# Bias_Lighting_Controller_Schematic.net
KiCad netlist of a schematic drawn in EAGLE
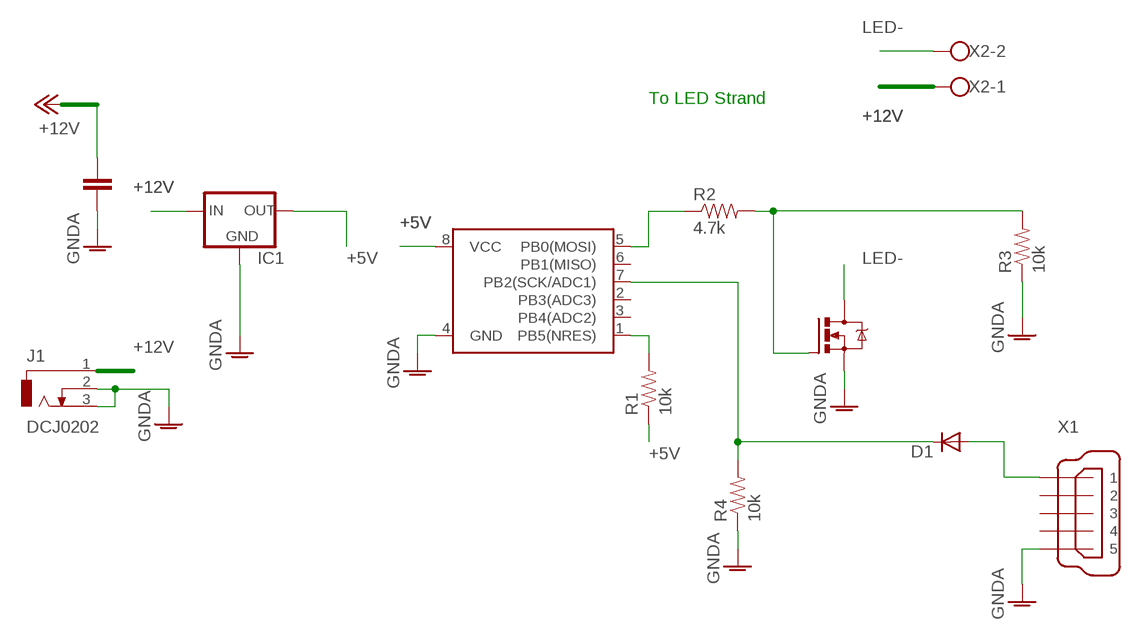
[diagram p0: schematic, sheet 1]

(export (version "E")
  (design (tool "Eeschema 10.0.6"))
  (components
    (comp (ref "C1")
      (value "CAP1206")
      (footprint "eagle-import:1206")
      (libsource (lib "eagle-import") (part "CAP1206"))
    )
    (comp (ref "D1")
      (value "DIODESMA")
      (footprint "eagle-import:SMA-DIODE")
      (libsource (lib "eagle-import") (part "DIODESMA"))
    )
    (comp (ref "IC1")
      (value "78LXX")
      (footprint "eagle-import:78LXX")
      (libsource (lib "eagle-import") (part "78LXX"))
    )
    (comp (ref "IRF740_MOSFET")
      (value "IRF740")
      (footprint "eagle-import:TO220BV")
      (libsource (lib "eagle-import") (part "IRF740"))
    )
    (comp (ref "J1")
      (value "DCJ0202")
      (footprint "eagle-import:DCJ0202")
      (libsource (lib "eagle-import") (part "DCJ0202"))
    )
    (comp (ref "R1")
      (value "10k")
      (footprint "eagle-import:1206")
      (libsource (lib "eagle-import") (part "RESISTOR1206"))
    )
    (comp (ref "R2")
      (value "4.7k")
      (footprint "eagle-import:1206")
      (libsource (lib "eagle-import") (part "RESISTOR1206"))
    )
    (comp (ref "R3")
      (value "10k")
      (footprint "eagle-import:1206")
      (libsource (lib "eagle-import") (part "RESISTOR1206"))
    )
    (comp (ref "R4")
      (value "10k")
      (footprint "eagle-import:1206")
      (libsource (lib "eagle-import") (part "RESISTOR1206"))
    )
    (comp (ref "U$1")
      (value "ATTINY45DIP8")
      (footprint "eagle-import:DIP08")
      (libsource (lib "eagle-import") (part "ATTINY45DIP8"))
    )
    (comp (ref "X1")
      (value "MINI-USB-UX60-MB-5ST")
      (footprint "eagle-import:UX60-MB-5ST")
      (libsource (lib "eagle-import") (part "MINI-USB-UX60-MB-5ST"))
    )
    (comp (ref "X2")
      (value "W237-102")
      (footprint "eagle-import:W237-102")
      (fields (field (name "MPN") "237-102"))
      (libsource (lib "eagle-import") (part "W237-102"))
    )
  )
  (nets
    (net (code "1") (name "+12V") (class "Default")
      (node (ref "C1") (pin "2") (pinfunction "2_2") (pintype "passive"))
      (node (ref "IC1") (pin "IN") (pinfunction "IN_IN") (pintype "input"))
      (node (ref "J1") (pin "1") (pinfunction "1_1") (pintype "passive"))
      (node (ref "X2") (pin "1") (pinfunction "KL_1") (pintype "passive"))
    )
    (net (code "2") (name "/+5V") (class "Default")
      (node (ref "IC1") (pin "OUT") (pinfunction "OUT_OUT") (pintype "passive"))
      (node (ref "R1") (pin "1") (pinfunction "1_1") (pintype "passive"))
      (node (ref "U$1") (pin "8") (pinfunction "VCC_8") (pintype "bidirectional"))
    )
    (net (code "3") (name "/LED-") (class "Default")
      (node (ref "IRF740_MOSFET") (pin "D") (pinfunction "D_D") (pintype "passive"))
      (node (ref "X2") (pin "2") (pinfunction "KL_2") (pintype "passive"))
    )
    (net (code "4") (name "GNDA") (class "Default")
      (node (ref "C1") (pin "1") (pinfunction "1_1") (pintype "passive"))
      (node (ref "IC1") (pin "GND") (pinfunction "GND_GND") (pintype "input"))
      (node (ref "IRF740_MOSFET") (pin "S") (pinfunction "S_S") (pintype "passive"))
      (node (ref "J1") (pin "2") (pinfunction "2_2") (pintype "passive"))
      (node (ref "J1") (pin "3") (pinfunction "3_3") (pintype "passive"))
      (node (ref "R3") (pin "1") (pinfunction "1_1") (pintype "passive"))
      (node (ref "R4") (pin "1") (pinfunction "1_1") (pintype "passive"))
      (node (ref "U$1") (pin "4") (pinfunction "GND_4") (pintype "bidirectional"))
      (node (ref "X1") (pin "5") (pinfunction "5_5") (pintype "input"))
    )
    (net (code "5") (name "Net-(D1-PadA)") (class "Default")
      (node (ref "D1") (pin "A") (pinfunction "A_A") (pintype "passive"))
      (node (ref "X1") (pin "1") (pinfunction "1_1") (pintype "input"))
    )
    (net (code "6") (name "Net-(IRF740_MOSFET-PadG)") (class "Default")
      (node (ref "IRF740_MOSFET") (pin "G") (pinfunction "G_G") (pintype "passive"))
      (node (ref "R2") (pin "2") (pinfunction "2_2") (pintype "passive"))
      (node (ref "R3") (pin "2") (pinfunction "2_2") (pintype "passive"))
    )
    (net (code "7") (name "Net-(U$1-PB0(MOSI))") (class "Default")
      (node (ref "R2") (pin "1") (pinfunction "1_1") (pintype "passive"))
      (node (ref "U$1") (pin "5") (pinfunction "PB0(MOSI)_5") (pintype "bidirectional"))
    )
    (net (code "8") (name "Net-(U$1-PB2(SCK{slash}ADC1))") (class "Default")
      (node (ref "D1") (pin "C") (pinfunction "C_C") (pintype "passive"))
      (node (ref "R4") (pin "2") (pinfunction "2_2") (pintype "passive"))
      (node (ref "U$1") (pin "7") (pinfunction "PB2(SCK/ADC1)_7") (pintype "bidirectional"))
    )
    (net (code "9") (name "Net-(U$1-PB5(NRES))") (class "Default")
      (node (ref "R1") (pin "2") (pinfunction "2_2") (pintype "passive"))
      (node (ref "U$1") (pin "1") (pinfunction "PB5(NRES)_1") (pintype "bidirectional"))
    )
    (net (code "10") (name "unconnected-(U$1-PB1(MISO)-Pad6)") (class "Default")
      (node (ref "U$1") (pin "6") (pinfunction "PB1(MISO)_6") (pintype "bidirectional"))
    )
    (net (code "11") (name "unconnected-(U$1-PB3(ADC3)-Pad2)") (class "Default")
      (node (ref "U$1") (pin "2") (pinfunction "PB3(ADC3)_2") (pintype "bidirectional"))
    )
    (net (code "12") (name "unconnected-(U$1-PB4(ADC2)-Pad3)") (class "Default")
      (node (ref "U$1") (pin "3") (pinfunction "PB4(ADC2)_3") (pintype "bidirectional"))
    )
    (net (code "13") (name "unconnected-(X1-Pad2)") (class "Default")
      (node (ref "X1") (pin "2") (pinfunction "2_2") (pintype "input"))
    )
    (net (code "14") (name "unconnected-(X1-Pad3)") (class "Default")
      (node (ref "X1") (pin "3") (pinfunction "3_3") (pintype "input"))
    )
    (net (code "15") (name "unconnected-(X1-Pad4)") (class "Default")
      (node (ref "X1") (pin "4") (pinfunction "4_4") (pintype "input"))
    )
  )
)
